# MainBoardSchematic.net
KiCad netlist of a schematic drawn in EAGLE
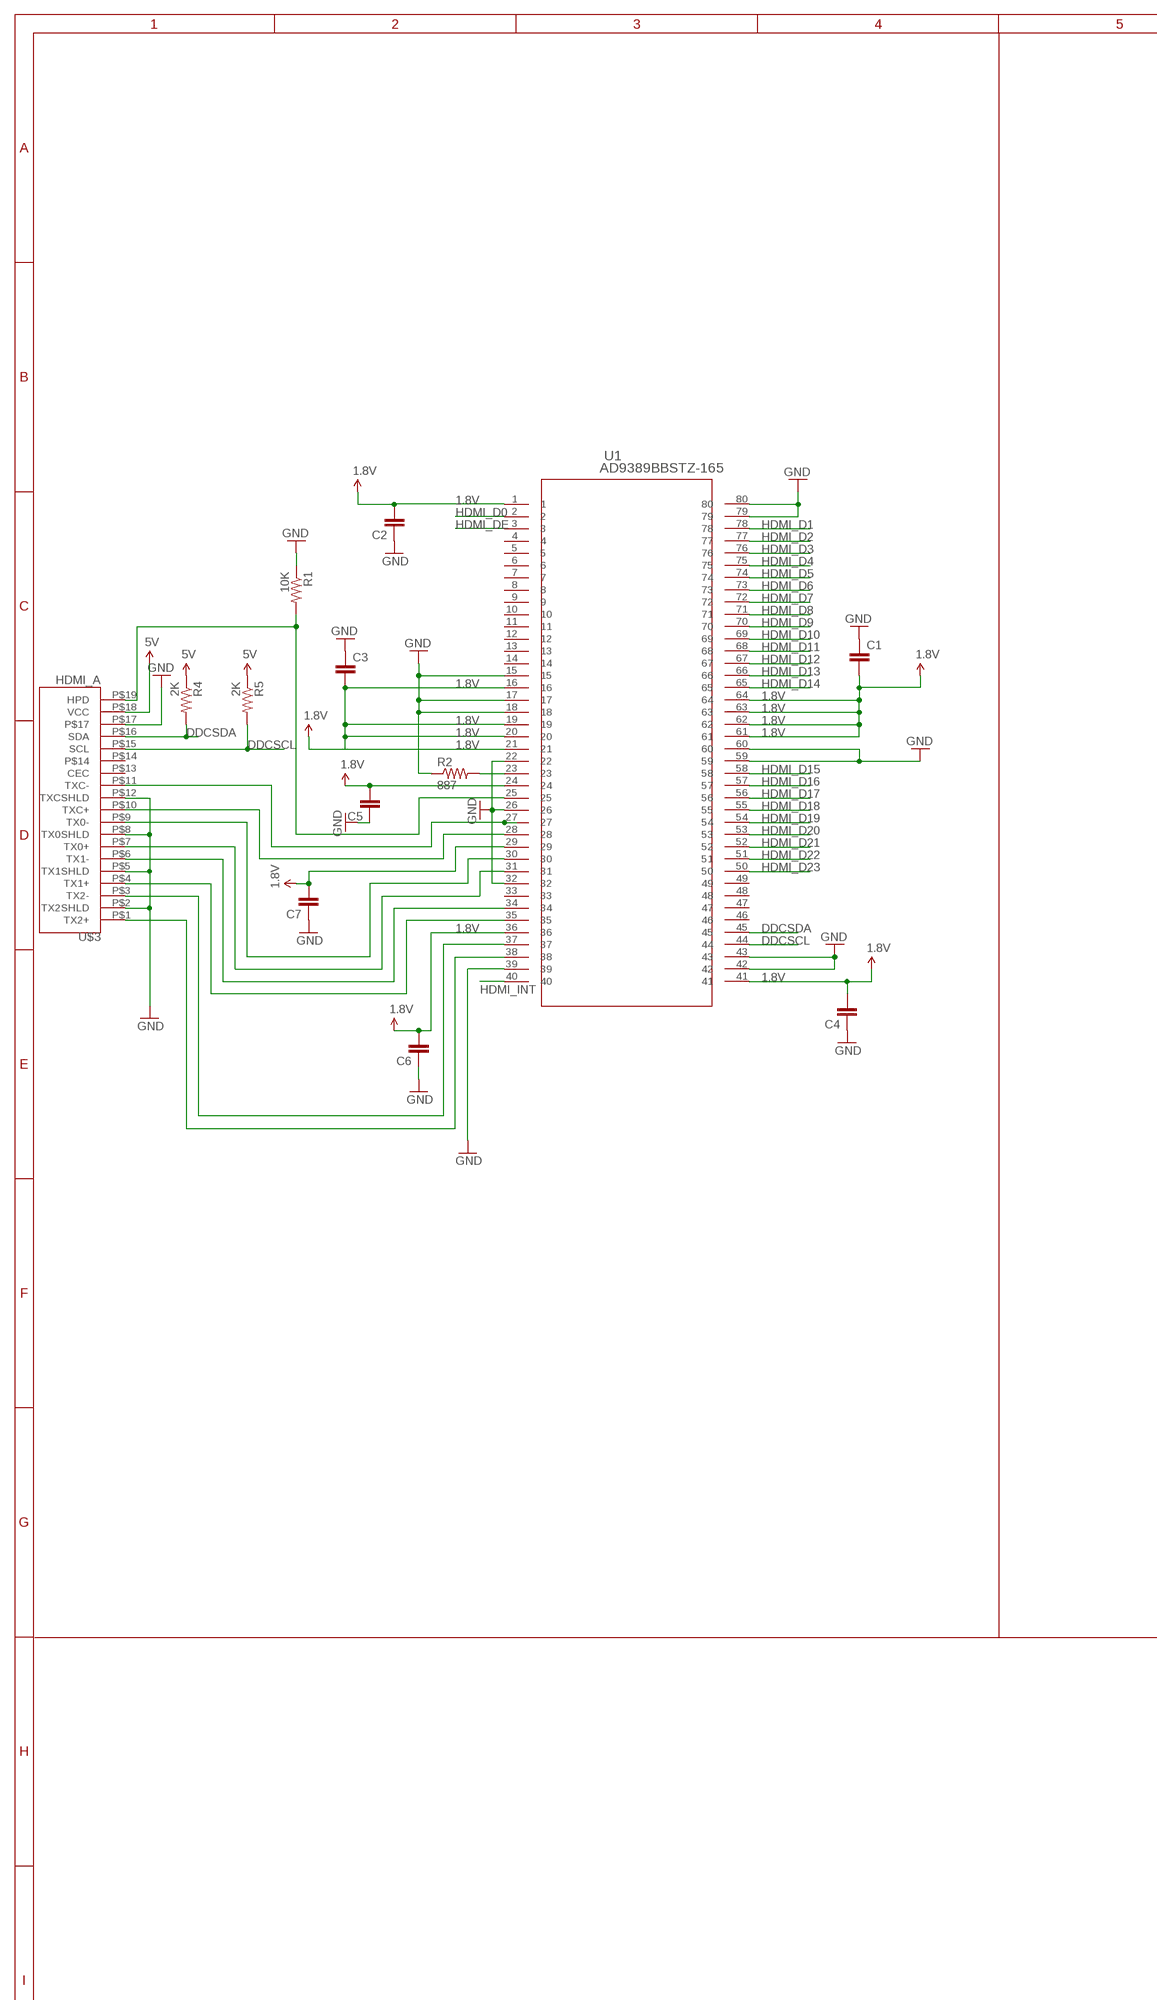
[diagram p0: schematic, sheet 1, part 1 of 2]
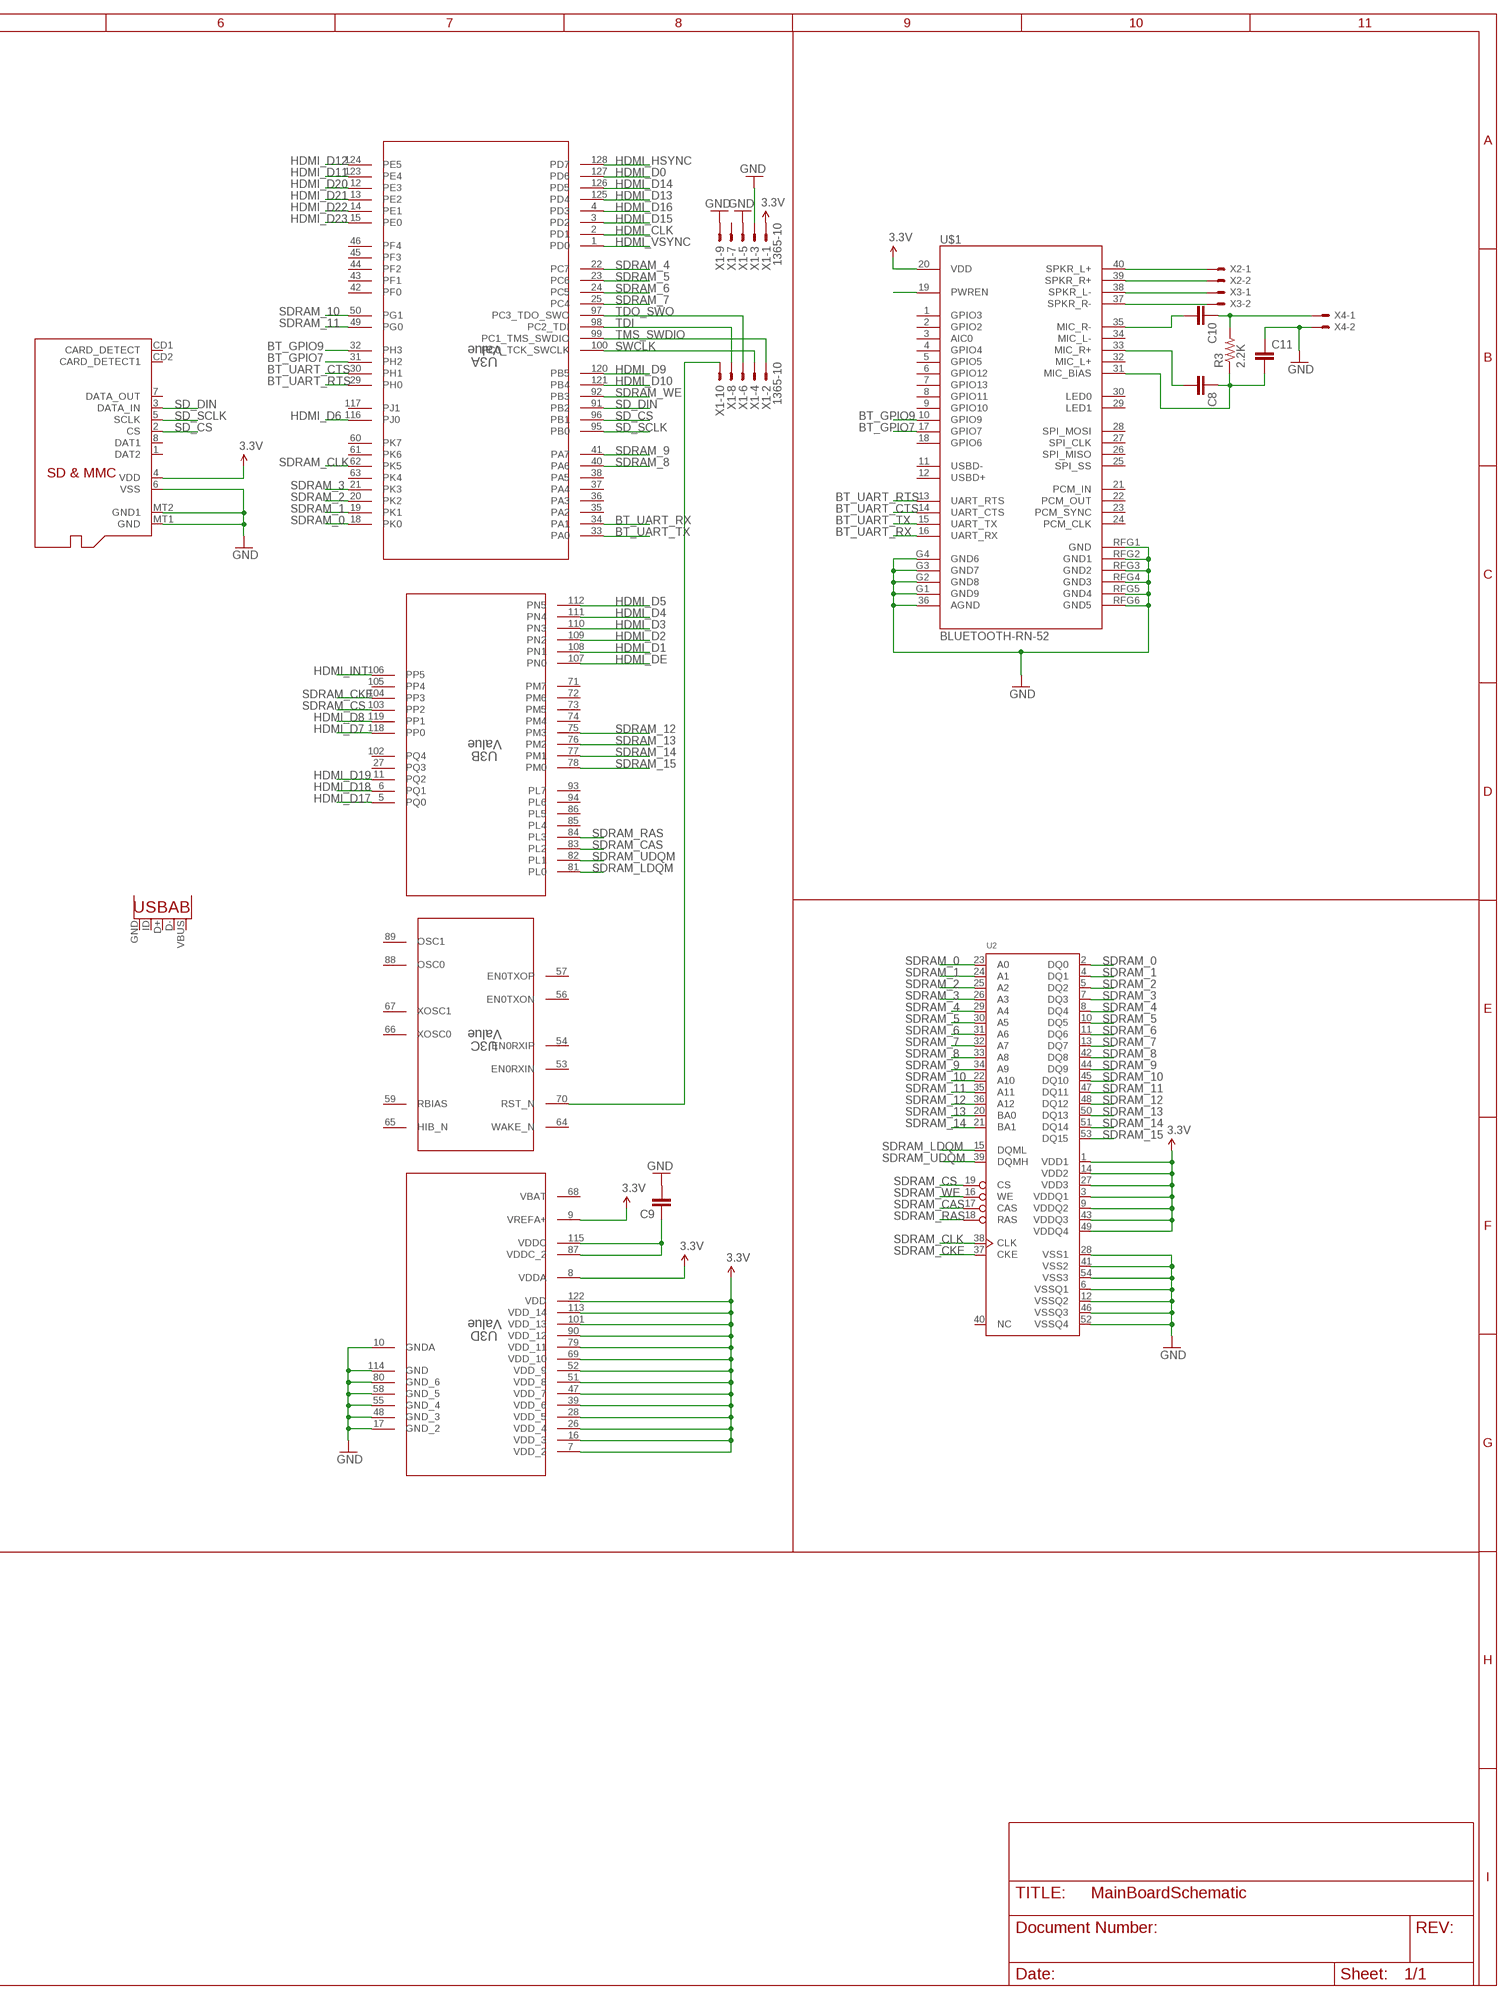
[diagram p1: schematic, sheet 1, part 2 of 2]

(export (version "E")
  (design (tool "Eeschema 10.0.6"))
  (components
    (comp (ref "C1")
      (value "0.1UF-50V-20%(PTH)KIT-EZ")
      (footprint "eagle-import:CAP-PTH-SMALL-KIT")
      (libsource (lib "eagle-import") (part "0.1UF-50V-20%(PTH)KIT-EZ"))
    )
    (comp (ref "C2")
      (value "0.1UF-50V-20%(PTH)KIT-EZ")
      (footprint "eagle-import:CAP-PTH-SMALL-KIT")
      (libsource (lib "eagle-import") (part "0.1UF-50V-20%(PTH)KIT-EZ"))
    )
    (comp (ref "C3")
      (value "0.1UF-50V-20%(PTH)KIT-EZ")
      (footprint "eagle-import:CAP-PTH-SMALL-KIT")
      (libsource (lib "eagle-import") (part "0.1UF-50V-20%(PTH)KIT-EZ"))
    )
    (comp (ref "C4")
      (value "0.1UF-50V-20%(PTH)KIT-EZ")
      (footprint "eagle-import:CAP-PTH-SMALL-KIT")
      (libsource (lib "eagle-import") (part "0.1UF-50V-20%(PTH)KIT-EZ"))
    )
    (comp (ref "C5")
      (value "0.1UF-50V-20%(PTH)KIT-EZ")
      (footprint "eagle-import:CAP-PTH-SMALL-KIT")
      (libsource (lib "eagle-import") (part "0.1UF-50V-20%(PTH)KIT-EZ"))
    )
    (comp (ref "C6")
      (value "0.1UF-50V-20%(PTH)KIT-EZ")
      (footprint "eagle-import:CAP-PTH-SMALL-KIT")
      (libsource (lib "eagle-import") (part "0.1UF-50V-20%(PTH)KIT-EZ"))
    )
    (comp (ref "C7")
      (value "0.1UF-50V-20%(PTH)KIT-EZ")
      (footprint "eagle-import:CAP-PTH-SMALL-KIT")
      (libsource (lib "eagle-import") (part "0.1UF-50V-20%(PTH)KIT-EZ"))
    )
    (comp (ref "C8")
      (value "0.1UF-50V-20%(PTH)KIT-EZ")
      (footprint "eagle-import:CAP-PTH-SMALL-KIT")
      (libsource (lib "eagle-import") (part "0.1UF-50V-20%(PTH)KIT-EZ"))
    )
    (comp (ref "C9")
      (value "0.1UF-50V-20%(PTH)KIT-EZ")
      (footprint "eagle-import:CAP-PTH-SMALL-KIT")
      (libsource (lib "eagle-import") (part "0.1UF-50V-20%(PTH)KIT-EZ"))
    )
    (comp (ref "C10")
      (value "0.1UF-50V-20%(PTH)KIT-EZ")
      (footprint "eagle-import:CAP-PTH-SMALL-KIT")
      (libsource (lib "eagle-import") (part "0.1UF-50V-20%(PTH)KIT-EZ"))
    )
    (comp (ref "C11")
      (value "0.1UF-50V-20%(PTH)KIT-EZ")
      (footprint "eagle-import:CAP-PTH-SMALL-KIT")
      (libsource (lib "eagle-import") (part "0.1UF-50V-20%(PTH)KIT-EZ"))
    )
    (comp (ref "R1")
      (value "10K")
      (footprint "eagle-import:1206")
      (libsource (lib "eagle-import") (part "RESISTOR1206"))
    )
    (comp (ref "R2")
      (value "887")
      (footprint "eagle-import:1206")
      (libsource (lib "eagle-import") (part "RESISTOR1206"))
    )
    (comp (ref "R3")
      (value "2.2K")
      (footprint "eagle-import:1206")
      (libsource (lib "eagle-import") (part "RESISTOR1206"))
    )
    (comp (ref "R4")
      (value "2K")
      (footprint "eagle-import:1206")
      (libsource (lib "eagle-import") (part "RESISTOR1206"))
    )
    (comp (ref "R5")
      (value "2K")
      (footprint "eagle-import:1206")
      (libsource (lib "eagle-import") (part "RESISTOR1206"))
    )
    (comp (ref "U$1")
      (value "BLUETOOTH-RN-52")
      (footprint "eagle-import:RN-52")
      (libsource (lib "eagle-import") (part "BLUETOOTH-RN-52"))
    )
    (comp (ref "U$2")
      (value "MICROSD")
      (footprint "eagle-import:MICROSD")
      (libsource (lib "eagle-import") (part "MICROSD"))
    )
    (comp (ref "U$3")
      (value "HDMI_A")
      (footprint "eagle-import:HDMI_A_SMD")
      (libsource (lib "eagle-import") (part "HDMI_A"))
    )
    (comp (ref "U1")
      (value "AD9389BBSTZ-165")
      (footprint "eagle-import:ST_80_2")
      (libsource (lib "eagle-import") (part "AD9389BBSTZ-165"))
    )
    (comp (ref "U2")
      (value "SDRAM_54TSOP")
      (footprint "eagle-import:TSOP54-400")
      (libsource (lib "eagle-import") (part "SDRAM_54TSOP"))
    )
    (comp (ref "U3")
      (value "Value")
      (footprint "eagle-import:PDT0128A_N")
      (fields
        (field (name "ALTERNATEPARTNUMBER") "TM4C129ENCPDTI3")
        (field (name "MANUFACTURER") "Texas Instruments")
        (field (name "PARTNUMBER") "TM4C129ENCPDTI3R")
      )
      (libsource (lib "eagle-import") (part "TM4C129ENCPDTI3R"))
    )
    (comp (ref "U4")
      (value "USB-AB")
      (footprint "eagle-import:USB-AB-MICRO-SMD")
      (libsource (lib "eagle-import") (part "USB-AB"))
    )
    (comp (ref "X1")
      (value "1365-10")
      (footprint "eagle-import:1365-10")
      (libsource (lib "eagle-import") (part "1365-10"))
    )
    (comp (ref "X2")
      (value "KK-156-2")
      (footprint "eagle-import:KK-156-2")
      (libsource (lib "eagle-import") (part "KK-156-2"))
    )
    (comp (ref "X3")
      (value "KK-156-2")
      (footprint "eagle-import:KK-156-2")
      (libsource (lib "eagle-import") (part "KK-156-2"))
    )
    (comp (ref "X4")
      (value "KK-156-2")
      (footprint "eagle-import:KK-156-2")
      (libsource (lib "eagle-import") (part "KK-156-2"))
    )
  )
  (nets
    (net (code "1") (name "/BT_GPIO7") (class "Default")
      (node (ref "U$1") (pin "17") (pinfunction "GPIO7_17") (pintype "bidirectional"))
      (node (ref "U3") (pin "31") (pinfunction "PH2_31") (pintype "bidirectional"))
    )
    (net (code "2") (name "/BT_GPIO9") (class "Default")
      (node (ref "U$1") (pin "10") (pinfunction "GPIO9_10") (pintype "bidirectional"))
      (node (ref "U3") (pin "32") (pinfunction "PH3_32") (pintype "bidirectional"))
    )
    (net (code "3") (name "/BT_UART_CTS") (class "Default")
      (node (ref "U$1") (pin "14") (pinfunction "UART_CTS_14") (pintype "bidirectional"))
      (node (ref "U3") (pin "30") (pinfunction "PH1_30") (pintype "bidirectional"))
    )
    (net (code "4") (name "/BT_UART_RTS") (class "Default")
      (node (ref "U$1") (pin "13") (pinfunction "UART_RTS_13") (pintype "bidirectional"))
      (node (ref "U3") (pin "29") (pinfunction "PH0_29") (pintype "bidirectional"))
    )
    (net (code "5") (name "/BT_UART_RX") (class "Default")
      (node (ref "U$1") (pin "16") (pinfunction "UART_RX_16") (pintype "bidirectional"))
      (node (ref "U3") (pin "34") (pinfunction "PA1_34") (pintype "bidirectional"))
    )
    (net (code "6") (name "/BT_UART_TX") (class "Default")
      (node (ref "U$1") (pin "15") (pinfunction "UART_TX_15") (pintype "bidirectional"))
      (node (ref "U3") (pin "33") (pinfunction "PA0_33") (pintype "bidirectional"))
    )
    (net (code "7") (name "/DDCSCL") (class "Default")
      (node (ref "R5") (pin "2") (pinfunction "2_2") (pintype "passive"))
      (node (ref "U$3") (pin "P$15") (pinfunction "SCL_P$15") (pintype "bidirectional"))
      (node (ref "U1") (pin "44") (pinfunction "44_44") (pintype "passive"))
    )
    (net (code "8") (name "/DDCSDA") (class "Default")
      (node (ref "R4") (pin "2") (pinfunction "2_2") (pintype "passive"))
      (node (ref "U$3") (pin "P$16") (pinfunction "SDA_P$16") (pintype "bidirectional"))
      (node (ref "U1") (pin "45") (pinfunction "45_45") (pintype "passive"))
    )
    (net (code "9") (name "/HDMI_CLK") (class "Default")
      (node (ref "U3") (pin "2") (pinfunction "PD1_2") (pintype "bidirectional"))
    )
    (net (code "10") (name "/HDMI_D0") (class "Default")
      (node (ref "U1") (pin "2") (pinfunction "2_2") (pintype "passive"))
      (node (ref "U3") (pin "127") (pinfunction "PD6_127") (pintype "bidirectional"))
    )
    (net (code "11") (name "/HDMI_D1") (class "Default")
      (node (ref "U1") (pin "78") (pinfunction "78_78") (pintype "passive"))
      (node (ref "U3") (pin "108") (pinfunction "PN1_108") (pintype "bidirectional"))
    )
    (net (code "12") (name "/HDMI_D2") (class "Default")
      (node (ref "U1") (pin "77") (pinfunction "77_77") (pintype "passive"))
      (node (ref "U3") (pin "109") (pinfunction "PN2_109") (pintype "bidirectional"))
    )
    (net (code "13") (name "/HDMI_D3") (class "Default")
      (node (ref "U1") (pin "76") (pinfunction "76_76") (pintype "passive"))
      (node (ref "U3") (pin "110") (pinfunction "PN3_110") (pintype "bidirectional"))
    )
    (net (code "14") (name "/HDMI_D4") (class "Default")
      (node (ref "U1") (pin "75") (pinfunction "75_75") (pintype "passive"))
      (node (ref "U3") (pin "111") (pinfunction "PN4_111") (pintype "bidirectional"))
    )
    (net (code "15") (name "/HDMI_D5") (class "Default")
      (node (ref "U1") (pin "74") (pinfunction "74_74") (pintype "passive"))
      (node (ref "U3") (pin "112") (pinfunction "PN5_112") (pintype "bidirectional"))
    )
    (net (code "16") (name "/HDMI_D6") (class "Default")
      (node (ref "U1") (pin "73") (pinfunction "73_73") (pintype "passive"))
      (node (ref "U3") (pin "116") (pinfunction "PJ0_116") (pintype "bidirectional"))
    )
    (net (code "17") (name "/HDMI_D7") (class "Default")
      (node (ref "U1") (pin "72") (pinfunction "72_72") (pintype "passive"))
      (node (ref "U3") (pin "118") (pinfunction "PP0_118") (pintype "bidirectional"))
    )
    (net (code "18") (name "/HDMI_D8") (class "Default")
      (node (ref "U1") (pin "71") (pinfunction "71_71") (pintype "passive"))
      (node (ref "U3") (pin "119") (pinfunction "PP1_119") (pintype "bidirectional"))
    )
    (net (code "19") (name "/HDMI_D9") (class "Default")
      (node (ref "U1") (pin "70") (pinfunction "70_70") (pintype "passive"))
      (node (ref "U3") (pin "120") (pinfunction "PB5_120") (pintype "bidirectional"))
    )
    (net (code "20") (name "/HDMI_D10") (class "Default")
      (node (ref "U1") (pin "69") (pinfunction "69_69") (pintype "passive"))
      (node (ref "U3") (pin "121") (pinfunction "PB4_121") (pintype "bidirectional"))
    )
    (net (code "21") (name "/HDMI_D11") (class "Default")
      (node (ref "U1") (pin "68") (pinfunction "68_68") (pintype "passive"))
      (node (ref "U3") (pin "123") (pinfunction "PE4_123") (pintype "bidirectional"))
    )
    (net (code "22") (name "/HDMI_D12") (class "Default")
      (node (ref "U1") (pin "67") (pinfunction "67_67") (pintype "passive"))
      (node (ref "U3") (pin "124") (pinfunction "PE5_124") (pintype "bidirectional"))
    )
    (net (code "23") (name "/HDMI_D13") (class "Default")
      (node (ref "U1") (pin "66") (pinfunction "66_66") (pintype "passive"))
      (node (ref "U3") (pin "125") (pinfunction "PD4_125") (pintype "bidirectional"))
    )
    (net (code "24") (name "/HDMI_D14") (class "Default")
      (node (ref "U1") (pin "65") (pinfunction "65_65") (pintype "passive"))
      (node (ref "U3") (pin "126") (pinfunction "PD5_126") (pintype "bidirectional"))
    )
    (net (code "25") (name "/HDMI_D15") (class "Default")
      (node (ref "U1") (pin "58") (pinfunction "58_58") (pintype "passive"))
      (node (ref "U3") (pin "3") (pinfunction "PD2_3") (pintype "bidirectional"))
    )
    (net (code "26") (name "/HDMI_D16") (class "Default")
      (node (ref "U1") (pin "57") (pinfunction "57_57") (pintype "passive"))
      (node (ref "U3") (pin "4") (pinfunction "PD3_4") (pintype "bidirectional"))
    )
    (net (code "27") (name "/HDMI_D17") (class "Default")
      (node (ref "U1") (pin "56") (pinfunction "56_56") (pintype "passive"))
      (node (ref "U3") (pin "5") (pinfunction "PQ0_5") (pintype "bidirectional"))
    )
    (net (code "28") (name "/HDMI_D18") (class "Default")
      (node (ref "U1") (pin "55") (pinfunction "55_55") (pintype "passive"))
      (node (ref "U3") (pin "6") (pinfunction "PQ1_6") (pintype "bidirectional"))
    )
    (net (code "29") (name "/HDMI_D19") (class "Default")
      (node (ref "U1") (pin "54") (pinfunction "54_54") (pintype "passive"))
      (node (ref "U3") (pin "11") (pinfunction "PQ2_11") (pintype "bidirectional"))
    )
    (net (code "30") (name "/HDMI_D20") (class "Default")
      (node (ref "U1") (pin "53") (pinfunction "53_53") (pintype "passive"))
      (node (ref "U3") (pin "12") (pinfunction "PE3_12") (pintype "bidirectional"))
    )
    (net (code "31") (name "/HDMI_D21") (class "Default")
      (node (ref "U1") (pin "52") (pinfunction "52_52") (pintype "passive"))
      (node (ref "U3") (pin "13") (pinfunction "PE2_13") (pintype "bidirectional"))
    )
    (net (code "32") (name "/HDMI_D22") (class "Default")
      (node (ref "U1") (pin "51") (pinfunction "51_51") (pintype "passive"))
      (node (ref "U3") (pin "14") (pinfunction "PE1_14") (pintype "bidirectional"))
    )
    (net (code "33") (name "/HDMI_D23") (class "Default")
      (node (ref "U1") (pin "50") (pinfunction "50_50") (pintype "passive"))
      (node (ref "U3") (pin "15") (pinfunction "PE0_15") (pintype "bidirectional"))
    )
    (net (code "34") (name "/HDMI_DE") (class "Default")
      (node (ref "U1") (pin "3") (pinfunction "3_3") (pintype "passive"))
      (node (ref "U3") (pin "107") (pinfunction "PN0_107") (pintype "bidirectional"))
    )
    (net (code "35") (name "/HDMI_HSYNC") (class "Default")
      (node (ref "U3") (pin "128") (pinfunction "PD7_128") (pintype "bidirectional"))
    )
    (net (code "36") (name "/HDMI_INT") (class "Default")
      (node (ref "U1") (pin "40") (pinfunction "40_40") (pintype "passive"))
      (node (ref "U3") (pin "106") (pinfunction "PP5_106") (pintype "bidirectional"))
    )
    (net (code "37") (name "/HDMI_VSYNC") (class "Default")
      (node (ref "U3") (pin "1") (pinfunction "PD0_1") (pintype "bidirectional"))
    )
    (net (code "38") (name "/SDRAM_0") (class "Default")
      (node (ref "U2") (pin "2") (pinfunction "DQ0_2") (pintype "bidirectional"))
      (node (ref "U2") (pin "23") (pinfunction "A0_23") (pintype "bidirectional"))
      (node (ref "U3") (pin "18") (pinfunction "PK0_18") (pintype "bidirectional"))
    )
    (net (code "39") (name "/SDRAM_1") (class "Default")
      (node (ref "U2") (pin "24") (pinfunction "A1_24") (pintype "bidirectional"))
      (node (ref "U2") (pin "4") (pinfunction "DQ1_4") (pintype "bidirectional"))
      (node (ref "U3") (pin "19") (pinfunction "PK1_19") (pintype "bidirectional"))
    )
    (net (code "40") (name "/SDRAM_2") (class "Default")
      (node (ref "U2") (pin "25") (pinfunction "A2_25") (pintype "bidirectional"))
      (node (ref "U2") (pin "5") (pinfunction "DQ2_5") (pintype "bidirectional"))
      (node (ref "U3") (pin "20") (pinfunction "PK2_20") (pintype "bidirectional"))
    )
    (net (code "41") (name "/SDRAM_3") (class "Default")
      (node (ref "U2") (pin "26") (pinfunction "A3_26") (pintype "bidirectional"))
      (node (ref "U2") (pin "7") (pinfunction "DQ3_7") (pintype "bidirectional"))
      (node (ref "U3") (pin "21") (pinfunction "PK3_21") (pintype "bidirectional"))
    )
    (net (code "42") (name "/SDRAM_4") (class "Default")
      (node (ref "U2") (pin "29") (pinfunction "A4_29") (pintype "bidirectional"))
      (node (ref "U2") (pin "8") (pinfunction "DQ4_8") (pintype "bidirectional"))
      (node (ref "U3") (pin "22") (pinfunction "PC7_22") (pintype "bidirectional"))
    )
    (net (code "43") (name "/SDRAM_5") (class "Default")
      (node (ref "U2") (pin "10") (pinfunction "DQ5_10") (pintype "bidirectional"))
      (node (ref "U2") (pin "30") (pinfunction "A5_30") (pintype "bidirectional"))
      (node (ref "U3") (pin "23") (pinfunction "PC6_23") (pintype "bidirectional"))
    )
    (net (code "44") (name "/SDRAM_6") (class "Default")
      (node (ref "U2") (pin "11") (pinfunction "DQ6_11") (pintype "bidirectional"))
      (node (ref "U2") (pin "31") (pinfunction "A6_31") (pintype "bidirectional"))
      (node (ref "U3") (pin "24") (pinfunction "PC5_24") (pintype "bidirectional"))
    )
    (net (code "45") (name "/SDRAM_7") (class "Default")
      (node (ref "U2") (pin "13") (pinfunction "DQ7_13") (pintype "bidirectional"))
      (node (ref "U2") (pin "32") (pinfunction "A7_32") (pintype "bidirectional"))
      (node (ref "U3") (pin "25") (pinfunction "PC4_25") (pintype "bidirectional"))
    )
    (net (code "46") (name "/SDRAM_8") (class "Default")
      (node (ref "U2") (pin "33") (pinfunction "A8_33") (pintype "bidirectional"))
      (node (ref "U2") (pin "42") (pinfunction "DQ8_42") (pintype "bidirectional"))
      (node (ref "U3") (pin "40") (pinfunction "PA6_40") (pintype "bidirectional"))
    )
    (net (code "47") (name "/SDRAM_9") (class "Default")
      (node (ref "U2") (pin "34") (pinfunction "A9_34") (pintype "bidirectional"))
      (node (ref "U2") (pin "44") (pinfunction "DQ9_44") (pintype "bidirectional"))
      (node (ref "U3") (pin "41") (pinfunction "PA7_41") (pintype "bidirectional"))
    )
    (net (code "48") (name "/SDRAM_10") (class "Default")
      (node (ref "U2") (pin "22") (pinfunction "A10_22") (pintype "bidirectional"))
      (node (ref "U2") (pin "45") (pinfunction "DQ10_45") (pintype "bidirectional"))
      (node (ref "U3") (pin "50") (pinfunction "PG1_50") (pintype "bidirectional"))
    )
    (net (code "49") (name "/SDRAM_11") (class "Default")
      (node (ref "U2") (pin "35") (pinfunction "A11_35") (pintype "bidirectional"))
      (node (ref "U2") (pin "47") (pinfunction "DQ11_47") (pintype "bidirectional"))
      (node (ref "U3") (pin "49") (pinfunction "PG0_49") (pintype "bidirectional"))
    )
    (net (code "50") (name "/SDRAM_12") (class "Default")
      (node (ref "U2") (pin "36") (pinfunction "A12_36") (pintype "bidirectional"))
      (node (ref "U2") (pin "48") (pinfunction "DQ12_48") (pintype "bidirectional"))
      (node (ref "U3") (pin "75") (pinfunction "PM3_75") (pintype "bidirectional"))
    )
    (net (code "51") (name "/SDRAM_13") (class "Default")
      (node (ref "U2") (pin "20") (pinfunction "BA0_20") (pintype "bidirectional"))
      (node (ref "U2") (pin "50") (pinfunction "DQ13_50") (pintype "bidirectional"))
      (node (ref "U3") (pin "76") (pinfunction "PM2_76") (pintype "bidirectional"))
    )
    (net (code "52") (name "/SDRAM_14") (class "Default")
      (node (ref "U2") (pin "21") (pinfunction "BA1_21") (pintype "bidirectional"))
      (node (ref "U2") (pin "51") (pinfunction "DQ14_51") (pintype "bidirectional"))
      (node (ref "U3") (pin "77") (pinfunction "PM1_77") (pintype "bidirectional"))
    )
    (net (code "53") (name "/SDRAM_15") (class "Default")
      (node (ref "U2") (pin "53") (pinfunction "DQ15_53") (pintype "bidirectional"))
      (node (ref "U3") (pin "78") (pinfunction "PM0_78") (pintype "bidirectional"))
    )
    (net (code "54") (name "/SDRAM_CAS") (class "Default")
      (node (ref "U2") (pin "17") (pinfunction "CAS_17") (pintype "bidirectional"))
      (node (ref "U3") (pin "83") (pinfunction "PL2_83") (pintype "bidirectional"))
    )
    (net (code "55") (name "/SDRAM_CKE") (class "Default")
      (node (ref "U2") (pin "37") (pinfunction "CKE_37") (pintype "bidirectional"))
      (node (ref "U3") (pin "104") (pinfunction "PP3_104") (pintype "bidirectional"))
    )
    (net (code "56") (name "/SDRAM_CLK") (class "Default")
      (node (ref "U2") (pin "38") (pinfunction "CLK_38") (pintype "bidirectional"))
      (node (ref "U3") (pin "62") (pinfunction "PK5_62") (pintype "bidirectional"))
    )
    (net (code "57") (name "/SDRAM_CS") (class "Default")
      (node (ref "U2") (pin "19") (pinfunction "CS_19") (pintype "bidirectional"))
      (node (ref "U3") (pin "103") (pinfunction "PP2_103") (pintype "bidirectional"))
    )
    (net (code "58") (name "/SDRAM_LDQM") (class "Default")
      (node (ref "U2") (pin "15") (pinfunction "DQML_15") (pintype "bidirectional"))
      (node (ref "U3") (pin "81") (pinfunction "PL0_81") (pintype "bidirectional"))
    )
    (net (code "59") (name "/SDRAM_RAS") (class "Default")
      (node (ref "U2") (pin "18") (pinfunction "RAS_18") (pintype "bidirectional"))
      (node (ref "U3") (pin "84") (pinfunction "PL3_84") (pintype "bidirectional"))
    )
    (net (code "60") (name "/SDRAM_UDQM") (class "Default")
      (node (ref "U2") (pin "39") (pinfunction "DQMH_39") (pintype "bidirectional"))
      (node (ref "U3") (pin "82") (pinfunction "PL1_82") (pintype "bidirectional"))
    )
    (net (code "61") (name "/SDRAM_WE") (class "Default")
      (node (ref "U2") (pin "16") (pinfunction "WE_16") (pintype "bidirectional"))
      (node (ref "U3") (pin "92") (pinfunction "PB3_92") (pintype "bidirectional"))
    )
    (net (code "62") (name "/SD_CS") (class "Default")
      (node (ref "U$2") (pin "2") (pinfunction "CS_2") (pintype "input"))
      (node (ref "U3") (pin "96") (pinfunction "PB1_96") (pintype "bidirectional"))
    )
    (net (code "63") (name "/SD_DIN") (class "Default")
      (node (ref "U$2") (pin "3") (pinfunction "DATA_IN_3") (pintype "input"))
      (node (ref "U3") (pin "91") (pinfunction "PB2_91") (pintype "bidirectional"))
    )
    (net (code "64") (name "/SD_SCLK") (class "Default")
      (node (ref "U$2") (pin "5") (pinfunction "SCLK_5") (pintype "input"))
      (node (ref "U3") (pin "95") (pinfunction "PB0_95") (pintype "bidirectional"))
    )
    (net (code "65") (name "/SWCLK") (class "Default")
      (node (ref "U3") (pin "100") (pinfunction "PC0_TCK_SWCLK_100") (pintype "bidirectional"))
      (node (ref "X1") (pin "4") (pinfunction "S_4") (pintype "passive"))
    )
    (net (code "66") (name "/TDI") (class "Default")
      (node (ref "U3") (pin "98") (pinfunction "PC2_TDI_98") (pintype "bidirectional"))
      (node (ref "X1") (pin "8") (pinfunction "S_8") (pintype "passive"))
    )
    (net (code "67") (name "/TDO_SWO") (class "Default")
      (node (ref "U3") (pin "97") (pinfunction "PC3_TDO_SWO_97") (pintype "bidirectional"))
      (node (ref "X1") (pin "6") (pinfunction "S_6") (pintype "passive"))
    )
    (net (code "68") (name "/TMS_SWDIO") (class "Default")
      (node (ref "U3") (pin "99") (pinfunction "PC1_TMS_SWDIO_99") (pintype "bidirectional"))
      (node (ref "X1") (pin "2") (pinfunction "S_2") (pintype "passive"))
    )
    (net (code "69") (name "/VBAT") (class "Default")
      (node (ref "U3") (pin "68") (pinfunction "VBAT_68") (pintype "power_in"))
    )
    (net (code "70") (name "1.8V") (class "Default")
      (node (ref "C1") (pin "2") (pinfunction "2_2") (pintype "passive"))
      (node (ref "C2") (pin "2") (pinfunction "2_2") (pintype "passive"))
      (node (ref "C3") (pin "2") (pinfunction "2_2") (pintype "passive"))
      (node (ref "C4") (pin "2") (pinfunction "2_2") (pintype "passive"))
      (node (ref "C5") (pin "2") (pinfunction "2_2") (pintype "passive"))
      (node (ref "C6") (pin "2") (pinfunction "2_2") (pintype "passive"))
      (node (ref "C7") (pin "2") (pinfunction "2_2") (pintype "passive"))
      (node (ref "U1") (pin "1") (pinfunction "1_1") (pintype "passive"))
      (node (ref "U1") (pin "16") (pinfunction "16_16") (pintype "passive"))
      (node (ref "U1") (pin "19") (pinfunction "19_19") (pintype "passive"))
      (node (ref "U1") (pin "20") (pinfunction "20_20") (pintype "passive"))
      (node (ref "U1") (pin "21") (pinfunction "21_21") (pintype "passive"))
      (node (ref "U1") (pin "24") (pinfunction "24_24") (pintype "passive"))
      (node (ref "U1") (pin "29") (pinfunction "29_29") (pintype "passive"))
      (node (ref "U1") (pin "36") (pinfunction "36_36") (pintype "passive"))
      (node (ref "U1") (pin "41") (pinfunction "41_41") (pintype "passive"))
      (node (ref "U1") (pin "61") (pinfunction "61_61") (pintype "passive"))
      (node (ref "U1") (pin "62") (pinfunction "62_62") (pintype "passive"))
      (node (ref "U1") (pin "63") (pinfunction "63_63") (pintype "passive"))
      (node (ref "U1") (pin "64") (pinfunction "64_64") (pintype "passive"))
    )
    (net (code "71") (name "3.3V") (class "Default")
      (node (ref "U$1") (pin "20") (pinfunction "VDD_20") (pintype "bidirectional"))
      (node (ref "U$2") (pin "4") (pinfunction "VDD_4") (pintype "power_in"))
      (node (ref "U2") (pin "1") (pinfunction "VDD1_1") (pintype "bidirectional"))
      (node (ref "U2") (pin "14") (pinfunction "VDD2_14") (pintype "bidirectional"))
      (node (ref "U2") (pin "27") (pinfunction "VDD3_27") (pintype "bidirectional"))
      (node (ref "U2") (pin "3") (pinfunction "VDDQ1_3") (pintype "bidirectional"))
      (node (ref "U2") (pin "43") (pinfunction "VDDQ3_43") (pintype "bidirectional"))
      (node (ref "U2") (pin "49") (pinfunction "VDDQ4_49") (pintype "bidirectional"))
      (node (ref "U2") (pin "9") (pinfunction "VDDQ2_9") (pintype "bidirectional"))
      (node (ref "U3") (pin "101") (pinfunction "VDD_13_101") (pintype "power_in"))
      (node (ref "U3") (pin "113") (pinfunction "VDD_14_113") (pintype "power_in"))
      (node (ref "U3") (pin "122") (pinfunction "VDD_122") (pintype "power_in"))
      (node (ref "U3") (pin "16") (pinfunction "VDD_3_16") (pintype "power_in"))
      (node (ref "U3") (pin "26") (pinfunction "VDD_4_26") (pintype "power_in"))
      (node (ref "U3") (pin "28") (pinfunction "VDD_5_28") (pintype "power_in"))
      (node (ref "U3") (pin "39") (pinfunction "VDD_6_39") (pintype "power_in"))
      (node (ref "U3") (pin "47") (pinfunction "VDD_7_47") (pintype "power_in"))
      (node (ref "U3") (pin "51") (pinfunction "VDD_8_51") (pintype "power_in"))
      (node (ref "U3") (pin "52") (pinfunction "VDD_9_52") (pintype "power_in"))
      (node (ref "U3") (pin "69") (pinfunction "VDD_10_69") (pintype "power_in"))
      (node (ref "U3") (pin "7") (pinfunction "VDD_2_7") (pintype "power_in"))
      (node (ref "U3") (pin "79") (pinfunction "VDD_11_79") (pintype "power_in"))
      (node (ref "U3") (pin "8") (pinfunction "VDDA_8") (pintype "power_in"))
      (node (ref "U3") (pin "9") (pinfunction "VREFA+_9") (pintype "power_in"))
      (node (ref "U3") (pin "90") (pinfunction "VDD_12_90") (pintype "power_in"))
      (node (ref "X1") (pin "1") (pinfunction "S_1") (pintype "passive"))
    )
    (net (code "72") (name "5V") (class "Default")
      (node (ref "R4") (pin "1") (pinfunction "1_1") (pintype "passive"))
      (node (ref "R5") (pin "1") (pinfunction "1_1") (pintype "passive"))
      (node (ref "U$3") (pin "P$18") (pinfunction "VCC_P$18") (pintype "bidirectional"))
    )
    (net (code "73") (name "GND") (class "Default")
      (node (ref "C1") (pin "1") (pinfunction "1_1") (pintype "passive"))
      (node (ref "C11") (pin "1") (pinfunction "1_1") (pintype "passive"))
      (node (ref "C2") (pin "1") (pinfunction "1_1") (pintype "passive"))
      (node (ref "C3") (pin "1") (pinfunction "1_1") (pintype "passive"))
      (node (ref "C4") (pin "1") (pinfunction "1_1") (pintype "passive"))
      (node (ref "C5") (pin "1") (pinfunction "1_1") (pintype "passive"))
      (node (ref "C6") (pin "1") (pinfunction "1_1") (pintype "passive"))
      (node (ref "C7") (pin "1") (pinfunction "1_1") (pintype "passive"))
      (node (ref "C9") (pin "2") (pinfunction "2_2") (pintype "passive"))
      (node (ref "R1") (pin "1") (pinfunction "1_1") (pintype "passive"))
      (node (ref "R2") (pin "1") (pinfunction "1_1") (pintype "passive"))
      (node (ref "U$1") (pin "36") (pinfunction "AGND_36") (pintype "bidirectional"))
      (node (ref "U$1") (pin "G1") (pinfunction "GND9_G1") (pintype "bidirectional"))
      (node (ref "U$1") (pin "G2") (pinfunction "GND8_G2") (pintype "bidirectional"))
      (node (ref "U$1") (pin "G3") (pinfunction "GND7_G3") (pintype "bidirectional"))
      (node (ref "U$1") (pin "G4") (pinfunction "GND6_G4") (pintype "bidirectional"))
      (node (ref "U$1") (pin "RFG1") (pinfunction "GND_RFG1") (pintype "bidirectional"))
      (node (ref "U$1") (pin "RFG2") (pinfunction "GND1_RFG2") (pintype "bidirectional"))
      (node (ref "U$1") (pin "RFG3") (pinfunction "GND2_RFG3") (pintype "bidirectional"))
      (node (ref "U$1") (pin "RFG4") (pinfunction "GND3_RFG4") (pintype "bidirectional"))
      (node (ref "U$1") (pin "RFG5") (pinfunction "GND4_RFG5") (pintype "bidirectional"))
      (node (ref "U$1") (pin "RFG6") (pinfunction "GND5_RFG6") (pintype "bidirectional"))
      (node (ref "U$2") (pin "6") (pinfunction "VSS_6") (pintype "power_in"))
      (node (ref "U$2") (pin "MT1") (pinfunction "GND_MT1") (pintype "power_in"))
      (node (ref "U$2") (pin "MT2") (pinfunction "GND1_MT2") (pintype "power_in"))
      (node (ref "U$3") (pin "P$12") (pinfunction "TXCSHLD_P$12") (pintype "bidirectional"))
      (node (ref "U$3") (pin "P$17") (pinfunction "P$17_P$17") (pintype "bidirectional"))
      (node (ref "U$3") (pin "P$2") (pinfunction "TX2SHLD_P$2") (pintype "bidirectional"))
      (node (ref "U$3") (pin "P$5") (pinfunction "TX1SHLD_P$5") (pintype "bidirectional"))
      (node (ref "U$3") (pin "P$8") (pinfunction "TX0SHLD_P$8") (pintype "bidirectional"))
      (node (ref "U1") (pin "15") (pinfunction "15_15") (pintype "passive"))
      (node (ref "U1") (pin "17") (pinfunction "17_17") (pintype "passive"))
      (node (ref "U1") (pin "18") (pinfunction "18_18") (pintype "passive"))
      (node (ref "U1") (pin "22") (pinfunction "22_22") (pintype "passive"))
      (node (ref "U1") (pin "26") (pinfunction "26_26") (pintype "passive"))
      (node (ref "U1") (pin "32") (pinfunction "32_32") (pintype "passive"))
      (node (ref "U1") (pin "39") (pinfunction "39_39") (pintype "passive"))
      (node (ref "U1") (pin "42") (pinfunction "42_42") (pintype "passive"))
      (node (ref "U1") (pin "43") (pinfunction "43_43") (pintype "passive"))
      (node (ref "U1") (pin "59") (pinfunction "59_59") (pintype "passive"))
      (node (ref "U1") (pin "60") (pinfunction "60_60") (pintype "passive"))
      (node (ref "U1") (pin "79") (pinfunction "79_79") (pintype "passive"))
      (node (ref "U1") (pin "80") (pinfunction "80_80") (pintype "passive"))
      (node (ref "U2") (pin "12") (pinfunction "VSSQ2_12") (pintype "bidirectional"))
      (node (ref "U2") (pin "28") (pinfunction "VSS1_28") (pintype "bidirectional"))
      (node (ref "U2") (pin "41") (pinfunction "VSS2_41") (pintype "bidirectional"))
      (node (ref "U2") (pin "46") (pinfunction "VSSQ3_46") (pintype "bidirectional"))
      (node (ref "U2") (pin "52") (pinfunction "VSSQ4_52") (pintype "bidirectional"))
      (node (ref "U2") (pin "54") (pinfunction "VSS3_54") (pintype "bidirectional"))
      (node (ref "U2") (pin "6") (pinfunction "VSSQ1_6") (pintype "bidirectional"))
      (node (ref "U3") (pin "10") (pinfunction "GNDA_10") (pintype "power_in"))
      (node (ref "U3") (pin "114") (pinfunction "GND_114") (pintype "power_in"))
      (node (ref "U3") (pin "17") (pinfunction "GND_2_17") (pintype "power_in"))
      (node (ref "U3") (pin "48") (pinfunction "GND_3_48") (pintype "power_in"))
      (node (ref "U3") (pin "55") (pinfunction "GND_4_55") (pintype "power_in"))
      (node (ref "U3") (pin "58") (pinfunction "GND_5_58") (pintype "power_in"))
      (node (ref "U3") (pin "80") (pinfunction "GND_6_80") (pintype "power_in"))
      (node (ref "X1") (pin "3") (pinfunction "S_3") (pintype "passive"))
      (node (ref "X1") (pin "5") (pinfunction "S_5") (pintype "passive"))
      (node (ref "X1") (pin "9") (pinfunction "S_9") (pintype "passive"))
      (node (ref "X4") (pin "2") (pinfunction "S_2") (pintype "passive"))
    )
    (net (code "74") (name "Net-(R2-Pad2)") (class "Default")
      (node (ref "R2") (pin "2") (pinfunction "2_2") (pintype "passive"))
      (node (ref "U1") (pin "23") (pinfunction "23_23") (pintype "passive"))
    )
    (net (code "75") (name "Net-(U$1-MIC_BIAS)") (class "Default")
      (node (ref "C11") (pin "2") (pinfunction "2_2") (pintype "passive"))
      (node (ref "C8") (pin "1") (pinfunction "1_1") (pintype "passive"))
      (node (ref "R3") (pin "1") (pinfunction "1_1") (pintype "passive"))
      (node (ref "U$1") (pin "31") (pinfunction "MIC_BIAS_31") (pintype "bidirectional"))
    )
    (net (code "76") (name "Net-(U$1-MIC_R+)") (class "Default")
      (node (ref "C8") (pin "2") (pinfunction "2_2") (pintype "passive"))
      (node (ref "U$1") (pin "33") (pinfunction "MIC_R+_33") (pintype "bidirectional"))
    )
    (net (code "77") (name "Net-(U$1-MIC_R-)") (class "Default")
      (node (ref "C10") (pin "2") (pinfunction "2_2") (pintype "passive"))
      (node (ref "U$1") (pin "35") (pinfunction "MIC_R-_35") (pintype "bidirectional"))
    )
    (net (code "78") (name "Net-(U$1-SPKR_L+)") (class "Default")
      (node (ref "U$1") (pin "40") (pinfunction "SPKR_L+_40") (pintype "bidirectional"))
      (node (ref "X2") (pin "1") (pinfunction "S_1") (pintype "passive"))
    )
    (net (code "79") (name "Net-(U$1-SPKR_L-)") (class "Default")
      (node (ref "U$1") (pin "38") (pinfunction "SPKR_L-_38") (pintype "bidirectional"))
      (node (ref "X3") (pin "1") (pinfunction "S_1") (pintype "passive"))
    )
    (net (code "80") (name "Net-(U$1-SPKR_R+)") (class "Default")
      (node (ref "U$1") (pin "39") (pinfunction "SPKR_R+_39") (pintype "bidirectional"))
      (node (ref "X2") (pin "2") (pinfunction "S_2") (pintype "passive"))
    )
    (net (code "81") (name "Net-(U$1-SPKR_R-)") (class "Default")
      (node (ref "U$1") (pin "37") (pinfunction "SPKR_R-_37") (pintype "bidirectional"))
      (node (ref "X3") (pin "2") (pinfunction "S_2") (pintype "passive"))
    )
    (net (code "82") (name "Net-(U$3-HPD)") (class "Default")
      (node (ref "R1") (pin "2") (pinfunction "2_2") (pintype "passive"))
      (node (ref "U$3") (pin "P$19") (pinfunction "HPD_P$19") (pintype "bidirectional"))
      (node (ref "U1") (pin "25") (pinfunction "25_25") (pintype "passive"))
    )
    (net (code "83") (name "Net-(U$3-TX0+)") (class "Default")
      (node (ref "U$3") (pin "P$7") (pinfunction "TX0+_P$7") (pintype "bidirectional"))
      (node (ref "U1") (pin "31") (pinfunction "31_31") (pintype "passive"))
    )
    (net (code "84") (name "Net-(U$3-TX0-)") (class "Default")
      (node (ref "U$3") (pin "P$9") (pinfunction "TX0-_P$9") (pintype "bidirectional"))
      (node (ref "U1") (pin "30") (pinfunction "30_30") (pintype "passive"))
    )
    (net (code "85") (name "Net-(U$3-TX1+)") (class "Default")
      (node (ref "U$3") (pin "P$4") (pinfunction "TX1+_P$4") (pintype "bidirectional"))
      (node (ref "U1") (pin "35") (pinfunction "35_35") (pintype "passive"))
    )
    (net (code "86") (name "Net-(U$3-TX1-)") (class "Default")
      (node (ref "U$3") (pin "P$6") (pinfunction "TX1-_P$6") (pintype "bidirectional"))
      (node (ref "U1") (pin "34") (pinfunction "34_34") (pintype "passive"))
    )
    (net (code "87") (name "Net-(U$3-TX2+)") (class "Default")
      (node (ref "U$3") (pin "P$1") (pinfunction "TX2+_P$1") (pintype "bidirectional"))
      (node (ref "U1") (pin "38") (pinfunction "38_38") (pintype "passive"))
    )
    (net (code "88") (name "Net-(U$3-TX2-)") (class "Default")
      (node (ref "U$3") (pin "P$3") (pinfunction "TX2-_P$3") (pintype "bidirectional"))
      (node (ref "U1") (pin "37") (pinfunction "37_37") (pintype "passive"))
    )
    (net (code "89") (name "Net-(U$3-TXC+)") (class "Default")
      (node (ref "U$3") (pin "P$10") (pinfunction "TXC+_P$10") (pintype "bidirectional"))
      (node (ref "U1") (pin "28") (pinfunction "28_28") (pintype "passive"))
    )
    (net (code "90") (name "Net-(U$3-TXC-)") (class "Default")
      (node (ref "U$3") (pin "P$11") (pinfunction "TXC-_P$11") (pintype "bidirectional"))
      (node (ref "U1") (pin "27") (pinfunction "27_27") (pintype "passive"))
    )
    (net (code "91") (name "Net-(U3C-RST_N)") (class "Default")
      (node (ref "U3") (pin "70") (pinfunction "RST_N_70") (pintype "input"))
      (node (ref "X1") (pin "10") (pinfunction "S_10") (pintype "passive"))
    )
    (net (code "92") (name "Net-(U3D-VDDC)") (class "Default")
      (node (ref "C9") (pin "1") (pinfunction "1_1") (pintype "passive"))
      (node (ref "U3") (pin "115") (pinfunction "VDDC_115") (pintype "power_in"))
      (node (ref "U3") (pin "87") (pinfunction "VDDC_2_87") (pintype "power_in"))
    )
    (net (code "93") (name "Net-(X4A-S)") (class "Default")
      (node (ref "C10") (pin "1") (pinfunction "1_1") (pintype "passive"))
      (node (ref "R3") (pin "2") (pinfunction "2_2") (pintype "passive"))
      (node (ref "X4") (pin "1") (pinfunction "S_1") (pintype "passive"))
    )
    (net (code "94") (name "unconnected-(U$1-AIC0-Pad3)") (class "Default")
      (node (ref "U$1") (pin "3") (pinfunction "AIC0_3") (pintype "bidirectional"))
    )
    (net (code "95") (name "unconnected-(U$1-GPIO2-Pad2)") (class "Default")
      (node (ref "U$1") (pin "2") (pinfunction "GPIO2_2") (pintype "bidirectional"))
    )
    (net (code "96") (name "unconnected-(U$1-GPIO3-Pad1)") (class "Default")
      (node (ref "U$1") (pin "1") (pinfunction "GPIO3_1") (pintype "bidirectional"))
    )
    (net (code "97") (name "unconnected-(U$1-GPIO4-Pad4)") (class "Default")
      (node (ref "U$1") (pin "4") (pinfunction "GPIO4_4") (pintype "bidirectional"))
    )
    (net (code "98") (name "unconnected-(U$1-GPIO5-Pad5)") (class "Default")
      (node (ref "U$1") (pin "5") (pinfunction "GPIO5_5") (pintype "bidirectional"))
    )
    (net (code "99") (name "unconnected-(U$1-GPIO6-Pad18)") (class "Default")
      (node (ref "U$1") (pin "18") (pinfunction "GPIO6_18") (pintype "bidirectional"))
    )
    (net (code "100") (name "unconnected-(U$1-GPIO10-Pad9)") (class "Default")
      (node (ref "U$1") (pin "9") (pinfunction "GPIO10_9") (pintype "bidirectional"))
    )
    (net (code "101") (name "unconnected-(U$1-GPIO11-Pad8)") (class "Default")
      (node (ref "U$1") (pin "8") (pinfunction "GPIO11_8") (pintype "bidirectional"))
    )
    (net (code "102") (name "unconnected-(U$1-GPIO12-Pad6)") (class "Default")
      (node (ref "U$1") (pin "6") (pinfunction "GPIO12_6") (pintype "bidirectional"))
    )
    (net (code "103") (name "unconnected-(U$1-GPIO13-Pad7)") (class "Default")
      (node (ref "U$1") (pin "7") (pinfunction "GPIO13_7") (pintype "bidirectional"))
    )
    (net (code "104") (name "unconnected-(U$1-LED0-Pad30)") (class "Default")
      (node (ref "U$1") (pin "30") (pinfunction "LED0_30") (pintype "bidirectional"))
    )
    (net (code "105") (name "unconnected-(U$1-LED1-Pad29)") (class "Default")
      (node (ref "U$1") (pin "29") (pinfunction "LED1_29") (pintype "bidirectional"))
    )
    (net (code "106") (name "unconnected-(U$1-MIC_L+-Pad32)") (class "Default")
      (node (ref "U$1") (pin "32") (pinfunction "MIC_L+_32") (pintype "bidirectional"))
    )
    (net (code "107") (name "unconnected-(U$1-MIC_L--Pad34)") (class "Default")
      (node (ref "U$1") (pin "34") (pinfunction "MIC_L-_34") (pintype "bidirectional"))
    )
    (net (code "108") (name "unconnected-(U$1-PCM_CLK-Pad24)") (class "Default")
      (node (ref "U$1") (pin "24") (pinfunction "PCM_CLK_24") (pintype "bidirectional"))
    )
    (net (code "109") (name "unconnected-(U$1-PCM_IN-Pad21)") (class "Default")
      (node (ref "U$1") (pin "21") (pinfunction "PCM_IN_21") (pintype "bidirectional"))
    )
    (net (code "110") (name "unconnected-(U$1-PCM_OUT-Pad22)") (class "Default")
      (node (ref "U$1") (pin "22") (pinfunction "PCM_OUT_22") (pintype "bidirectional"))
    )
    (net (code "111") (name "unconnected-(U$1-PCM_SYNC-Pad23)") (class "Default")
      (node (ref "U$1") (pin "23") (pinfunction "PCM_SYNC_23") (pintype "bidirectional"))
    )
    (net (code "112") (name "unconnected-(U$1-PWREN-Pad19)") (class "Default")
      (node (ref "U$1") (pin "19") (pinfunction "PWREN_19") (pintype "bidirectional"))
    )
    (net (code "113") (name "unconnected-(U$1-SPI_CLK-Pad27)") (class "Default")
      (node (ref "U$1") (pin "27") (pinfunction "SPI_CLK_27") (pintype "bidirectional"))
    )
    (net (code "114") (name "unconnected-(U$1-SPI_MISO-Pad26)") (class "Default")
      (node (ref "U$1") (pin "26") (pinfunction "SPI_MISO_26") (pintype "bidirectional"))
    )
    (net (code "115") (name "unconnected-(U$1-SPI_MOSI-Pad28)") (class "Default")
      (node (ref "U$1") (pin "28") (pinfunction "SPI_MOSI_28") (pintype "bidirectional"))
    )
    (net (code "116") (name "unconnected-(U$1-SPI_SS-Pad25)") (class "Default")
      (node (ref "U$1") (pin "25") (pinfunction "SPI_SS_25") (pintype "bidirectional"))
    )
    (net (code "117") (name "unconnected-(U$1-USBD+-Pad12)") (class "Default")
      (node (ref "U$1") (pin "12") (pinfunction "USBD+_12") (pintype "bidirectional"))
    )
    (net (code "118") (name "unconnected-(U$1-USBD--Pad11)") (class "Default")
      (node (ref "U$1") (pin "11") (pinfunction "USBD-_11") (pintype "bidirectional"))
    )
    (net (code "119") (name "unconnected-(U$2-CARD_DETECT-PadCD1)") (class "Default")
      (node (ref "U$2") (pin "CD1") (pinfunction "CARD_DETECT_CD1") (pintype "passive"))
    )
    (net (code "120") (name "unconnected-(U$2-CARD_DETECT1-PadCD2)") (class "Default")
      (node (ref "U$2") (pin "CD2") (pinfunction "CARD_DETECT1_CD2") (pintype "passive"))
    )
    (net (code "121") (name "unconnected-(U$2-DAT1-Pad8)") (class "Default")
      (node (ref "U$2") (pin "8") (pinfunction "DAT1_8") (pintype "bidirectional"))
    )
    (net (code "122") (name "unconnected-(U$2-DAT2-Pad1)") (class "Default")
      (node (ref "U$2") (pin "1") (pinfunction "DAT2_1") (pintype "bidirectional"))
    )
    (net (code "123") (name "unconnected-(U$2-DATA_OUT-Pad7)") (class "Default")
      (node (ref "U$2") (pin "7") (pinfunction "DATA_OUT_7") (pintype "output"))
    )
    (net (code "124") (name "unconnected-(U$3-CEC-PadP$13)") (class "Default")
      (node (ref "U$3") (pin "P$13") (pinfunction "CEC_P$13") (pintype "bidirectional"))
    )
    (net (code "125") (name "unconnected-(U$3-PadP$14)") (class "Default")
      (node (ref "U$3") (pin "P$14") (pinfunction "P$14_P$14") (pintype "bidirectional"))
    )
    (net (code "126") (name "unconnected-(U1-Pad4)") (class "Default")
      (node (ref "U1") (pin "4") (pinfunction "4_4") (pintype "passive"))
    )
    (net (code "127") (name "unconnected-(U1-Pad5)") (class "Default")
      (node (ref "U1") (pin "5") (pinfunction "5_5") (pintype "passive"))
    )
    (net (code "128") (name "unconnected-(U1-Pad6)") (class "Default")
      (node (ref "U1") (pin "6") (pinfunction "6_6") (pintype "passive"))
    )
    (net (code "129") (name "unconnected-(U1-Pad7)") (class "Default")
      (node (ref "U1") (pin "7") (pinfunction "7_7") (pintype "passive"))
    )
    (net (code "130") (name "unconnected-(U1-Pad8)") (class "Default")
      (node (ref "U1") (pin "8") (pinfunction "8_8") (pintype "passive"))
    )
    (net (code "131") (name "unconnected-(U1-Pad9)") (class "Default")
      (node (ref "U1") (pin "9") (pinfunction "9_9") (pintype "passive"))
    )
    (net (code "132") (name "unconnected-(U1-Pad10)") (class "Default")
      (node (ref "U1") (pin "10") (pinfunction "10_10") (pintype "passive"))
    )
    (net (code "133") (name "unconnected-(U1-Pad11)") (class "Default")
      (node (ref "U1") (pin "11") (pinfunction "11_11") (pintype "passive"))
    )
    (net (code "134") (name "unconnected-(U1-Pad12)") (class "Default")
      (node (ref "U1") (pin "12") (pinfunction "12_12") (pintype "passive"))
    )
    (net (code "135") (name "unconnected-(U1-Pad13)") (class "Default")
      (node (ref "U1") (pin "13") (pinfunction "13_13") (pintype "passive"))
    )
    (net (code "136") (name "unconnected-(U1-Pad14)") (class "Default")
      (node (ref "U1") (pin "14") (pinfunction "14_14") (pintype "passive"))
    )
    (net (code "137") (name "unconnected-(U1-Pad33)") (class "Default")
      (node (ref "U1") (pin "33") (pinfunction "33_33") (pintype "passive"))
    )
    (net (code "138") (name "unconnected-(U1-Pad46)") (class "Default")
      (node (ref "U1") (pin "46") (pinfunction "46_46") (pintype "passive"))
    )
    (net (code "139") (name "unconnected-(U1-Pad47)") (class "Default")
      (node (ref "U1") (pin "47") (pinfunction "47_47") (pintype "passive"))
    )
    (net (code "140") (name "unconnected-(U1-Pad48)") (class "Default")
      (node (ref "U1") (pin "48") (pinfunction "48_48") (pintype "passive"))
    )
    (net (code "141") (name "unconnected-(U1-Pad49)") (class "Default")
      (node (ref "U1") (pin "49") (pinfunction "49_49") (pintype "passive"))
    )
    (net (code "142") (name "unconnected-(U2-NC-Pad40)") (class "Default")
      (node (ref "U2") (pin "40") (pinfunction "NC_40") (pintype "bidirectional"))
    )
    (net (code "143") (name "unconnected-(U3A-PA2-Pad35)") (class "Default")
      (node (ref "U3") (pin "35") (pinfunction "PA2_35") (pintype "bidirectional"))
    )
    (net (code "144") (name "unconnected-(U3A-PA3-Pad36)") (class "Default")
      (node (ref "U3") (pin "36") (pinfunction "PA3_36") (pintype "bidirectional"))
    )
    (net (code "145") (name "unconnected-(U3A-PA4-Pad37)") (class "Default")
      (node (ref "U3") (pin "37") (pinfunction "PA4_37") (pintype "bidirectional"))
    )
    (net (code "146") (name "unconnected-(U3A-PA5-Pad38)") (class "Default")
      (node (ref "U3") (pin "38") (pinfunction "PA5_38") (pintype "bidirectional"))
    )
    (net (code "147") (name "unconnected-(U3A-PF0-Pad42)") (class "Default")
      (node (ref "U3") (pin "42") (pinfunction "PF0_42") (pintype "bidirectional"))
    )
    (net (code "148") (name "unconnected-(U3A-PF1-Pad43)") (class "Default")
      (node (ref "U3") (pin "43") (pinfunction "PF1_43") (pintype "bidirectional"))
    )
    (net (code "149") (name "unconnected-(U3A-PF2-Pad44)") (class "Default")
      (node (ref "U3") (pin "44") (pinfunction "PF2_44") (pintype "bidirectional"))
    )
    (net (code "150") (name "unconnected-(U3A-PF3-Pad45)") (class "Default")
      (node (ref "U3") (pin "45") (pinfunction "PF3_45") (pintype "bidirectional"))
    )
    (net (code "151") (name "unconnected-(U3A-PF4-Pad46)") (class "Default")
      (node (ref "U3") (pin "46") (pinfunction "PF4_46") (pintype "bidirectional"))
    )
    (net (code "152") (name "unconnected-(U3A-PJ1-Pad117)") (class "Default")
      (node (ref "U3") (pin "117") (pinfunction "PJ1_117") (pintype "bidirectional"))
    )
    (net (code "153") (name "unconnected-(U3A-PK4-Pad63)") (class "Default")
      (node (ref "U3") (pin "63") (pinfunction "PK4_63") (pintype "bidirectional"))
    )
    (net (code "154") (name "unconnected-(U3A-PK6-Pad61)") (class "Default")
      (node (ref "U3") (pin "61") (pinfunction "PK6_61") (pintype "bidirectional"))
    )
    (net (code "155") (name "unconnected-(U3A-PK7-Pad60)") (class "Default")
      (node (ref "U3") (pin "60") (pinfunction "PK7_60") (pintype "bidirectional"))
    )
    (net (code "156") (name "unconnected-(U3B-PL4-Pad85)") (class "Default")
      (node (ref "U3") (pin "85") (pinfunction "PL4_85") (pintype "bidirectional"))
    )
    (net (code "157") (name "unconnected-(U3B-PL5-Pad86)") (class "Default")
      (node (ref "U3") (pin "86") (pinfunction "PL5_86") (pintype "bidirectional"))
    )
    (net (code "158") (name "unconnected-(U3B-PL6-Pad94)") (class "Default")
      (node (ref "U3") (pin "94") (pinfunction "PL6_94") (pintype "bidirectional"))
    )
    (net (code "159") (name "unconnected-(U3B-PL7-Pad93)") (class "Default")
      (node (ref "U3") (pin "93") (pinfunction "PL7_93") (pintype "bidirectional"))
    )
    (net (code "160") (name "unconnected-(U3B-PM4-Pad74)") (class "Default")
      (node (ref "U3") (pin "74") (pinfunction "PM4_74") (pintype "bidirectional"))
    )
    (net (code "161") (name "unconnected-(U3B-PM5-Pad73)") (class "Default")
      (node (ref "U3") (pin "73") (pinfunction "PM5_73") (pintype "bidirectional"))
    )
    (net (code "162") (name "unconnected-(U3B-PM6-Pad72)") (class "Default")
      (node (ref "U3") (pin "72") (pinfunction "PM6_72") (pintype "bidirectional"))
    )
    (net (code "163") (name "unconnected-(U3B-PM7-Pad71)") (class "Default")
      (node (ref "U3") (pin "71") (pinfunction "PM7_71") (pintype "bidirectional"))
    )
    (net (code "164") (name "unconnected-(U3B-PP4-Pad105)") (class "Default")
      (node (ref "U3") (pin "105") (pinfunction "PP4_105") (pintype "bidirectional"))
    )
    (net (code "165") (name "unconnected-(U3B-PQ3-Pad27)") (class "Default")
      (node (ref "U3") (pin "27") (pinfunction "PQ3_27") (pintype "bidirectional"))
    )
    (net (code "166") (name "unconnected-(U3B-PQ4-Pad102)") (class "Default")
      (node (ref "U3") (pin "102") (pinfunction "PQ4_102") (pintype "bidirectional"))
    )
    (net (code "167") (name "unconnected-(U3C-EN0RXIN-Pad53)") (class "Default")
      (node (ref "U3") (pin "53") (pinfunction "EN0RXIN_53") (pintype "bidirectional"))
    )
    (net (code "168") (name "unconnected-(U3C-EN0RXIP-Pad54)") (class "Default")
      (node (ref "U3") (pin "54") (pinfunction "EN0RXIP_54") (pintype "bidirectional"))
    )
    (net (code "169") (name "unconnected-(U3C-EN0TXON-Pad56)") (class "Default")
      (node (ref "U3") (pin "56") (pinfunction "EN0TXON_56") (pintype "bidirectional"))
    )
    (net (code "170") (name "unconnected-(U3C-EN0TXOP-Pad57)") (class "Default")
      (node (ref "U3") (pin "57") (pinfunction "EN0TXOP_57") (pintype "bidirectional"))
    )
    (net (code "171") (name "unconnected-(U3C-HIB_N-Pad65)") (class "Default")
      (node (ref "U3") (pin "65") (pinfunction "HIB_N_65") (pintype "output"))
    )
    (net (code "172") (name "unconnected-(U3C-OSC0-Pad88)") (class "Default")
      (node (ref "U3") (pin "88") (pinfunction "OSC0_88") (pintype "input"))
    )
    (net (code "173") (name "unconnected-(U3C-OSC1-Pad89)") (class "Default")
      (node (ref "U3") (pin "89") (pinfunction "OSC1_89") (pintype "output"))
    )
    (net (code "174") (name "unconnected-(U3C-RBIAS-Pad59)") (class "Default")
      (node (ref "U3") (pin "59") (pinfunction "RBIAS_59") (pintype "output"))
    )
    (net (code "175") (name "unconnected-(U3C-WAKE_N-Pad64)") (class "Default")
      (node (ref "U3") (pin "64") (pinfunction "WAKE_N_64") (pintype "input"))
    )
    (net (code "176") (name "unconnected-(U3C-XOSC0-Pad66)") (class "Default")
      (node (ref "U3") (pin "66") (pinfunction "XOSC0_66") (pintype "input"))
    )
    (net (code "177") (name "unconnected-(U3C-XOSC1-Pad67)") (class "Default")
      (node (ref "U3") (pin "67") (pinfunction "XOSC1_67") (pintype "output"))
    )
    (net (code "178") (name "unconnected-(U4-PadD+)") (class "Default")
      (node (ref "U4") (pin "D+") (pinfunction "D+_D+") (pintype "bidirectional"))
    )
    (net (code "179") (name "unconnected-(U4-PadD-)") (class "Default")
      (node (ref "U4") (pin "D-") (pinfunction "D-_D-") (pintype "bidirectional"))
    )
    (net (code "180") (name "unconnected-(U4-PadGND)") (class "Default")
      (node (ref "U4") (pin "GND") (pinfunction "GND_GND") (pintype "bidirectional"))
    )
    (net (code "181") (name "unconnected-(U4-PadVBUS)") (class "Default")
      (node (ref "U4") (pin "VBUS") (pinfunction "VBUS_VBUS") (pintype "bidirectional"))
    )
    (net (code "182") (name "unconnected-(U4-USBID-PadID)") (class "Default")
      (node (ref "U4") (pin "ID") (pinfunction "USBID_ID") (pintype "bidirectional"))
    )
    (net (code "183") (name "unconnected-(X1H-S-Pad7)") (class "Default")
      (node (ref "X1") (pin "7") (pinfunction "S_7") (pintype "passive"))
    )
  )
)
